# Tardis.net
KiCad netlist of a schematic drawn in EAGLE
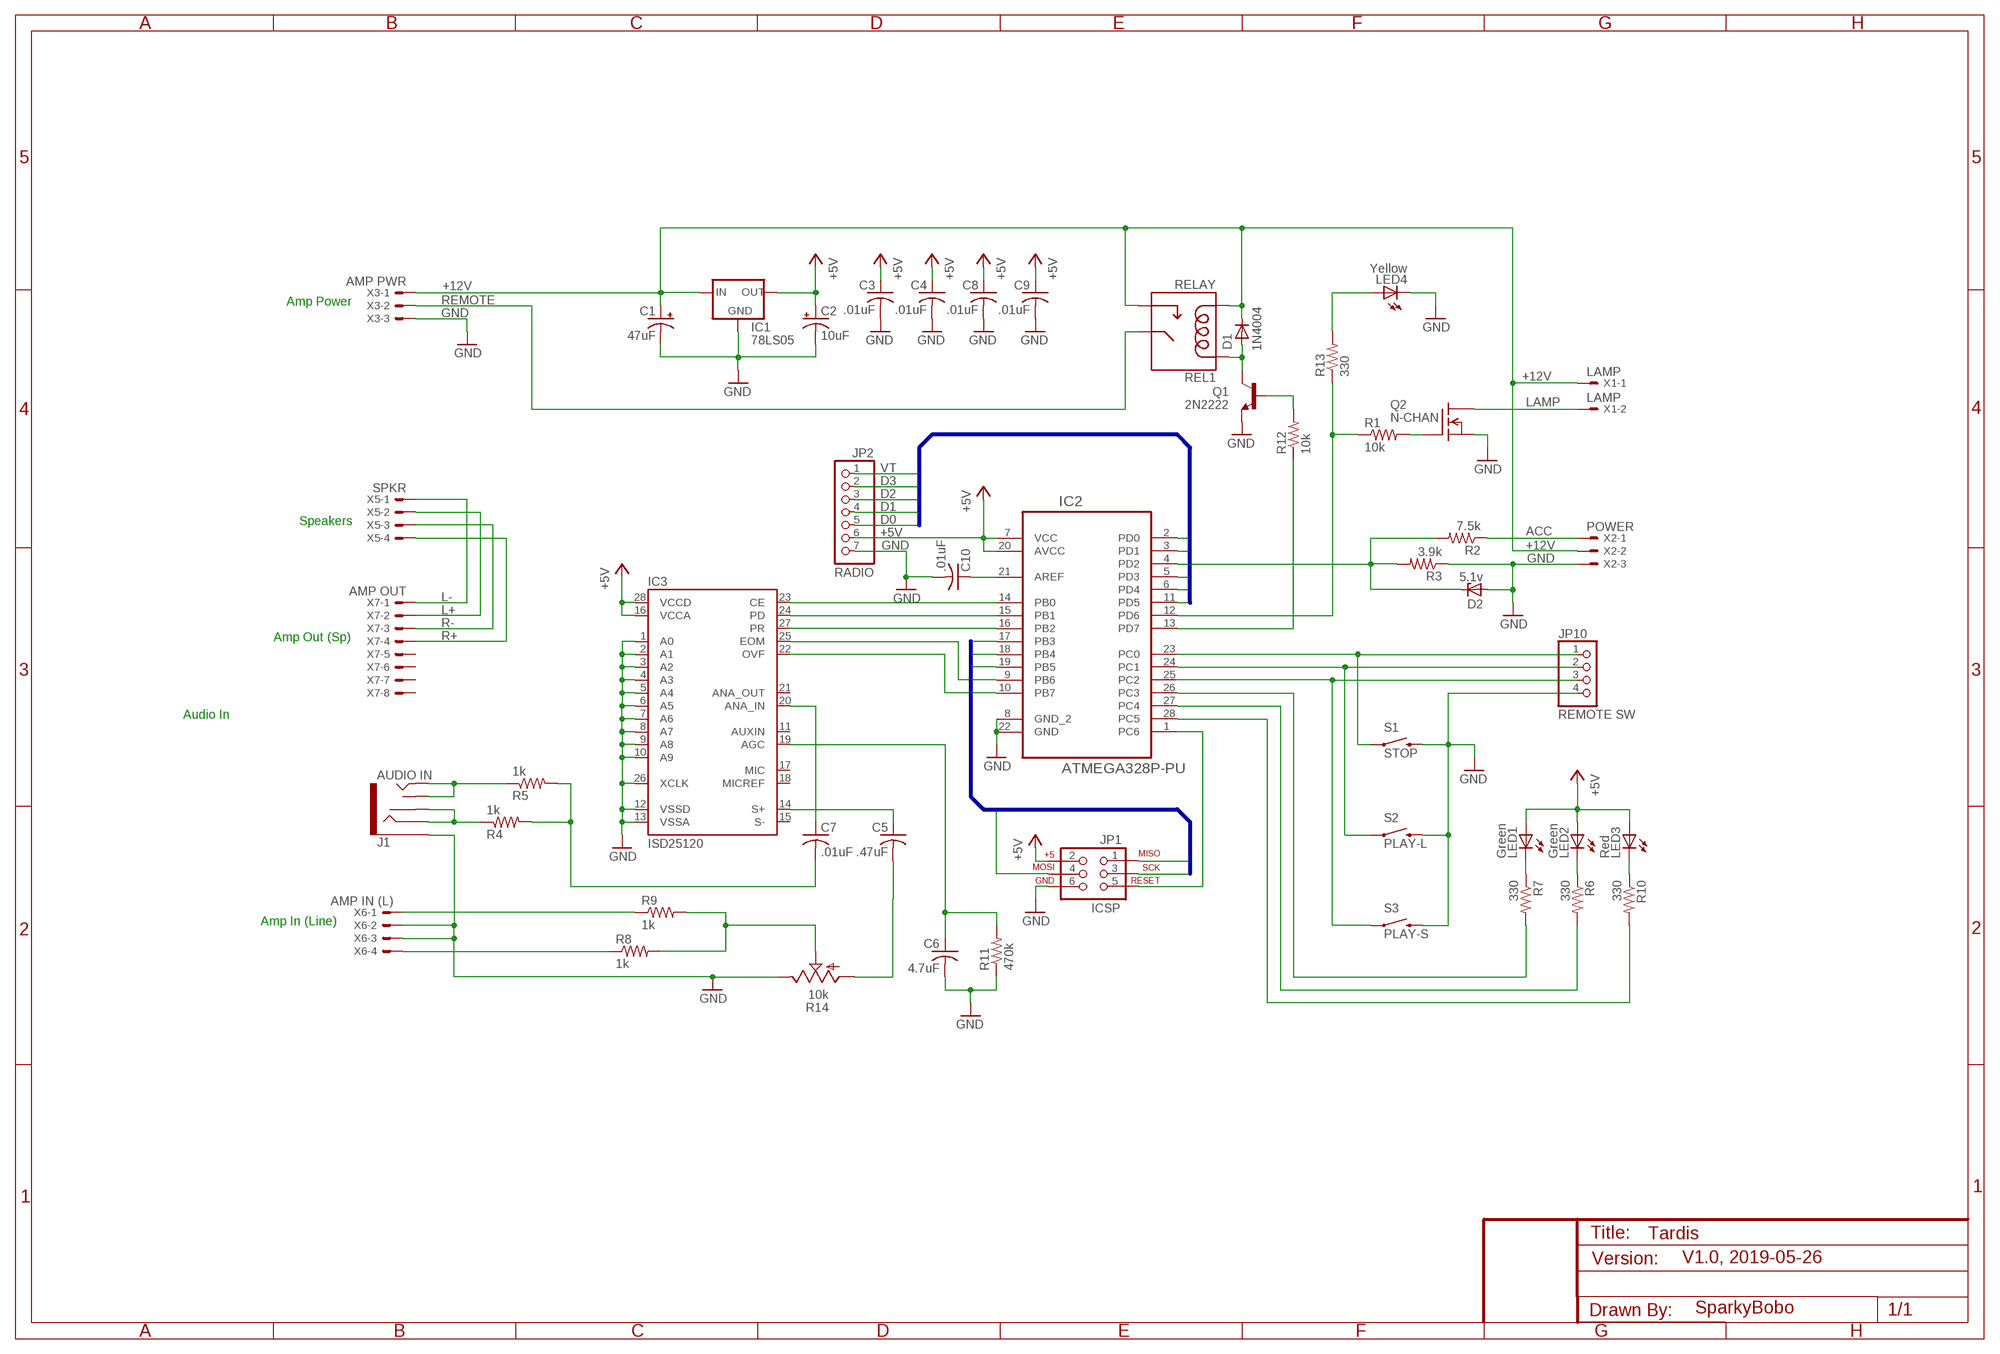
[diagram p0: schematic, sheet 1]

(export (version "E")
  (design (tool "Eeschema 10.0.6"))
  (components
    (comp (ref "C1")
      (value "47uF")
      (footprint "eagle-import:E3,5-8")
      (libsource (lib "eagle-import") (part "CPOL-USE3.5-8"))
    )
    (comp (ref "C2")
      (value "10uF")
      (footprint "eagle-import:E3,5-8")
      (libsource (lib "eagle-import") (part "CPOL-USE3.5-8"))
    )
    (comp (ref "C3")
      (value ".01uF")
      (footprint "eagle-import:C025-025X050")
      (libsource (lib "eagle-import") (part "C-US025-025X050"))
    )
    (comp (ref "C4")
      (value ".01uF")
      (footprint "eagle-import:C025-025X050")
      (libsource (lib "eagle-import") (part "C-US025-025X050"))
    )
    (comp (ref "C5")
      (value ".47uF")
      (footprint "eagle-import:C025-025X050")
      (libsource (lib "eagle-import") (part "C-US025-025X050"))
    )
    (comp (ref "C6")
      (value "4.7uF")
      (footprint "eagle-import:C025-025X050")
      (libsource (lib "eagle-import") (part "C-US025-025X050"))
    )
    (comp (ref "C7")
      (value ".01uF")
      (footprint "eagle-import:C050-025X075")
      (libsource (lib "eagle-import") (part "C-US050-025X075"))
    )
    (comp (ref "C8")
      (value ".01uF")
      (footprint "eagle-import:C025-025X050")
      (libsource (lib "eagle-import") (part "C-US025-025X050"))
    )
    (comp (ref "C9")
      (value ".01uF")
      (footprint "eagle-import:C025-025X050")
      (libsource (lib "eagle-import") (part "C-US025-025X050"))
    )
    (comp (ref "C10")
      (value ".01uF")
      (footprint "eagle-import:C025-025X050")
      (libsource (lib "eagle-import") (part "C-US025-025X050"))
    )
    (comp (ref "D1")
      (value "1N4004")
      (footprint "eagle-import:DIODE-1N4148")
      (libsource (lib "eagle-import") (part "DIODE1N4148"))
    )
    (comp (ref "D2")
      (value "5.1v")
      (footprint "eagle-import:DO35Z10")
      (libsource (lib "eagle-import") (part "ZENER-DIODEDO35Z10"))
    )
    (comp (ref "IC1")
      (value "78LS05")
      (footprint "eagle-import:TO-92")
      (libsource (lib "eagle-import") (part "V_REG_78XXTO-92"))
    )
    (comp (ref "IC2")
      (value "ATMEGA328P-PU")
      (footprint "eagle-import:DIP254P762X457-28")
      (libsource (lib "eagle-import") (part "ATMEGA328P-PU"))
    )
    (comp (ref "IC3")
      (value "ISD25120")
      (footprint "eagle-import:CRAZYGIRAFFE_DIL28-6")
      (libsource (lib "eagle-import") (part "CRAZYGIRAFFE_ISD25120"))
    )
    (comp (ref "J1")
      (value "AUDIO IN")
      (footprint "eagle-import:AUDIO-JACK")
      (libsource (lib "eagle-import") (part "AUDIO-JACK2PTH"))
    )
    (comp (ref "JP1")
      (value "ICSP")
      (footprint "eagle-import:2X3")
      (libsource (lib "eagle-import") (part "AVR_SPI_PRG_6PTH"))
    )
    (comp (ref "JP2")
      (value "RADIO")
      (footprint "eagle-import:1X07")
      (libsource (lib "eagle-import") (part "PINHD-1X7"))
    )
    (comp (ref "JP10")
      (value "REMOTE SW")
      (footprint "eagle-import:1X04")
      (libsource (lib "eagle-import") (part "PINHD-1X4"))
    )
    (comp (ref "LED1")
      (value "Green")
      (footprint "eagle-import:LED5MM")
      (libsource (lib "eagle-import") (part "LED5MM"))
    )
    (comp (ref "LED2")
      (value "Green")
      (footprint "eagle-import:LED5MM")
      (libsource (lib "eagle-import") (part "LED5MM"))
    )
    (comp (ref "LED3")
      (value "Red")
      (footprint "eagle-import:LED5MM")
      (libsource (lib "eagle-import") (part "LED5MM"))
    )
    (comp (ref "LED4")
      (value "Yellow")
      (footprint "eagle-import:LED5MM")
      (libsource (lib "eagle-import") (part "LED5MM"))
    )
    (comp (ref "Q1")
      (value "2N2222")
      (footprint "eagle-import:TO-92")
      (libsource (lib "eagle-import") (part "TRANSISTOR_NPNTO92"))
    )
    (comp (ref "Q2")
      (value "N-CHAN")
      (footprint "eagle-import:TO220")
      (libsource (lib "eagle-import") (part "BUZ10"))
    )
    (comp (ref "R1")
      (value "10k")
      (footprint "eagle-import:0207_10")
      (libsource (lib "eagle-import") (part "R-US_0207/10"))
    )
    (comp (ref "R2")
      (value "7.5k")
      (footprint "eagle-import:0207_10")
      (libsource (lib "eagle-import") (part "R-US_0207/10"))
    )
    (comp (ref "R3")
      (value "3.9k")
      (footprint "eagle-import:0207_10")
      (libsource (lib "eagle-import") (part "R-US_0207/10"))
    )
    (comp (ref "R4")
      (value "1k")
      (footprint "eagle-import:0207_10")
      (libsource (lib "eagle-import") (part "R-US_0207/10"))
    )
    (comp (ref "R5")
      (value "1k")
      (footprint "eagle-import:0207_10")
      (libsource (lib "eagle-import") (part "R-US_0207/10"))
    )
    (comp (ref "R6")
      (value "330")
      (footprint "eagle-import:0207_10")
      (libsource (lib "eagle-import") (part "R-US_0207/10"))
    )
    (comp (ref "R7")
      (value "330")
      (footprint "eagle-import:0207_10")
      (libsource (lib "eagle-import") (part "R-US_0207/10"))
    )
    (comp (ref "R8")
      (value "1k")
      (footprint "eagle-import:0207_10")
      (libsource (lib "eagle-import") (part "R-US_0207/10"))
    )
    (comp (ref "R9")
      (value "1k")
      (footprint "eagle-import:0207_10")
      (libsource (lib "eagle-import") (part "R-US_0207/10"))
    )
    (comp (ref "R10")
      (value "330")
      (footprint "eagle-import:0207_10")
      (libsource (lib "eagle-import") (part "R-US_0207/10"))
    )
    (comp (ref "R11")
      (value "470k")
      (footprint "eagle-import:0207_10")
      (libsource (lib "eagle-import") (part "R-US_0207/10"))
    )
    (comp (ref "R12")
      (value "10k")
      (footprint "eagle-import:0207_10")
      (libsource (lib "eagle-import") (part "R-US_0207/10"))
    )
    (comp (ref "R13")
      (value "330")
      (footprint "eagle-import:0207_10")
      (libsource (lib "eagle-import") (part "R-US_0207/10"))
    )
    (comp (ref "R14")
      (value "10k")
      (footprint "eagle-import:CA6V")
      (libsource (lib "eagle-import") (part "TRIM_US-CA6V"))
    )
    (comp (ref "REL1")
      (value "RELAY")
      (footprint "eagle-import:CRAZYGIRAFFE_RELAY-DIP")
      (libsource (lib "eagle-import") (part "CRAZYGIRAFFE_RELAY"))
    )
    (comp (ref "S1")
      (value "STOP")
      (footprint "eagle-import:CRAZYGIRAFFE_TACTILE-PTH-12MM")
      (libsource (lib "eagle-import") (part "CRAZYGIRAFFE_SWITCH-MOMENTARY-212MM"))
    )
    (comp (ref "S2")
      (value "PLAY-L")
      (footprint "eagle-import:CRAZYGIRAFFE_TACTILE-PTH-12MM")
      (libsource (lib "eagle-import") (part "CRAZYGIRAFFE_SWITCH-MOMENTARY-212MM"))
    )
    (comp (ref "S3")
      (value "PLAY-S")
      (footprint "eagle-import:CRAZYGIRAFFE_TACTILE-PTH-12MM")
      (libsource (lib "eagle-import") (part "CRAZYGIRAFFE_SWITCH-MOMENTARY-212MM"))
    )
    (comp (ref "X1")
      (value "LAMP")
      (footprint "eagle-import:KK-156-2")
      (libsource (lib "eagle-import") (part "KK-156-2"))
    )
    (comp (ref "X2")
      (value "POWER")
      (footprint "eagle-import:KK-156-3")
      (libsource (lib "eagle-import") (part "KK-156-3"))
    )
    (comp (ref "X3")
      (value "AMP PWR")
      (footprint "eagle-import:KK-156-3")
      (libsource (lib "eagle-import") (part "KK-156-3"))
    )
    (comp (ref "X5")
      (value "SPKR")
      (footprint "eagle-import:KK-156-4")
      (libsource (lib "eagle-import") (part "KK-156-4"))
    )
    (comp (ref "X6")
      (value "AMP IN (L)")
      (footprint "eagle-import:KK-156-4")
      (libsource (lib "eagle-import") (part "KK-156-4"))
    )
    (comp (ref "X7")
      (value "AMP OUT")
      (footprint "eagle-import:KK-156-8")
      (libsource (lib "eagle-import") (part "KK-156-8"))
    )
  )
  (nets
    (net (code "1") (name "+5V") (class "Default")
      (node (ref "C2") (pin "+") (pinfunction "+_+") (pintype "passive"))
      (node (ref "C3") (pin "1") (pinfunction "1_1") (pintype "passive"))
      (node (ref "C4") (pin "1") (pinfunction "1_1") (pintype "passive"))
      (node (ref "C8") (pin "1") (pinfunction "1_1") (pintype "passive"))
      (node (ref "C9") (pin "1") (pinfunction "1_1") (pintype "passive"))
      (node (ref "IC1") (pin "3") (pinfunction "OUT_3") (pintype "output"))
      (node (ref "IC2") (pin "20") (pinfunction "AVCC_20") (pintype "power_in"))
      (node (ref "IC2") (pin "7") (pinfunction "VCC_7") (pintype "power_in"))
      (node (ref "IC3") (pin "16") (pinfunction "VCCA_16") (pintype "power_in"))
      (node (ref "IC3") (pin "28") (pinfunction "VCCD_28") (pintype "power_in"))
      (node (ref "JP1") (pin "2") (pinfunction "2_2") (pintype "passive"))
      (node (ref "JP2") (pin "6") (pinfunction "6_6") (pintype "passive"))
      (node (ref "LED1") (pin "A") (pinfunction "A_A") (pintype "passive"))
      (node (ref "LED2") (pin "A") (pinfunction "A_A") (pintype "passive"))
      (node (ref "LED3") (pin "A") (pinfunction "A_A") (pintype "passive"))
    )
    (net (code "2") (name "/+12V") (class "Default")
      (node (ref "C1") (pin "+") (pinfunction "+_+") (pintype "passive"))
      (node (ref "D1") (pin "C") (pinfunction "C_C") (pintype "passive"))
      (node (ref "IC1") (pin "2") (pinfunction "IN_2") (pintype "input"))
      (node (ref "REL1") (pin "2") (pinfunction "COIL2_2") (pintype "bidirectional"))
      (node (ref "REL1") (pin "4") (pinfunction "NO_4") (pintype "bidirectional"))
      (node (ref "X1") (pin "1") (pinfunction "S_1") (pintype "passive"))
      (node (ref "X2") (pin "2") (pinfunction "S_2") (pintype "passive"))
      (node (ref "X3") (pin "1") (pinfunction "S_1") (pintype "passive"))
    )
    (net (code "3") (name "/ACC") (class "Default")
      (node (ref "R2") (pin "1") (pinfunction "1_1") (pintype "passive"))
      (node (ref "X2") (pin "1") (pinfunction "S_1") (pintype "passive"))
    )
    (net (code "4") (name "/D0") (class "Default")
      (node (ref "IC2") (pin "3") (pinfunction "PD1_3") (pintype "bidirectional"))
      (node (ref "JP2") (pin "5") (pinfunction "5_5") (pintype "passive"))
    )
    (net (code "5") (name "/D1") (class "Default")
      (node (ref "IC2") (pin "2") (pinfunction "PD0_2") (pintype "bidirectional"))
      (node (ref "JP2") (pin "4") (pinfunction "4_4") (pintype "passive"))
    )
    (net (code "6") (name "/D2") (class "Default")
      (node (ref "IC2") (pin "11") (pinfunction "PD5_11") (pintype "bidirectional"))
      (node (ref "JP2") (pin "3") (pinfunction "3_3") (pintype "passive"))
    )
    (net (code "7") (name "/D3") (class "Default")
      (node (ref "IC2") (pin "6") (pinfunction "PD4_6") (pintype "bidirectional"))
      (node (ref "JP2") (pin "2") (pinfunction "2_2") (pintype "passive"))
    )
    (net (code "8") (name "/L+") (class "Default")
      (node (ref "X5") (pin "2") (pinfunction "S_2") (pintype "passive"))
      (node (ref "X7") (pin "2") (pinfunction "S_2") (pintype "passive"))
    )
    (net (code "9") (name "/L-") (class "Default")
      (node (ref "X5") (pin "1") (pinfunction "S_1") (pintype "passive"))
      (node (ref "X7") (pin "1") (pinfunction "S_1") (pintype "passive"))
    )
    (net (code "10") (name "/LAMP") (class "Default")
      (node (ref "Q2") (pin "2") (pinfunction "D_2") (pintype "passive"))
      (node (ref "X1") (pin "2") (pinfunction "S_2") (pintype "passive"))
    )
    (net (code "11") (name "/MISO") (class "Default")
      (node (ref "IC2") (pin "18") (pinfunction "PB4_18") (pintype "bidirectional"))
      (node (ref "JP1") (pin "1") (pinfunction "1_1") (pintype "passive"))
    )
    (net (code "12") (name "/MOSI") (class "Default")
      (node (ref "IC2") (pin "17") (pinfunction "PB3_17") (pintype "bidirectional"))
      (node (ref "JP1") (pin "4") (pinfunction "4_4") (pintype "passive"))
    )
    (net (code "13") (name "/R+") (class "Default")
      (node (ref "X5") (pin "4") (pinfunction "S_4") (pintype "passive"))
      (node (ref "X7") (pin "4") (pinfunction "S_4") (pintype "passive"))
    )
    (net (code "14") (name "/R-") (class "Default")
      (node (ref "X5") (pin "3") (pinfunction "S_3") (pintype "passive"))
      (node (ref "X7") (pin "3") (pinfunction "S_3") (pintype "passive"))
    )
    (net (code "15") (name "/REMOTE") (class "Default")
      (node (ref "REL1") (pin "3") (pinfunction "MAIN_3") (pintype "bidirectional"))
      (node (ref "X3") (pin "2") (pinfunction "S_2") (pintype "passive"))
    )
    (net (code "16") (name "/SCK") (class "Default")
      (node (ref "IC2") (pin "19") (pinfunction "PB5_19") (pintype "bidirectional"))
      (node (ref "JP1") (pin "3") (pinfunction "3_3") (pintype "passive"))
    )
    (net (code "17") (name "/VT") (class "Default")
      (node (ref "IC2") (pin "5") (pinfunction "PD3_5") (pintype "bidirectional"))
      (node (ref "JP2") (pin "1") (pinfunction "1_1") (pintype "passive"))
    )
    (net (code "18") (name "GND") (class "Default")
      (node (ref "C1") (pin "-") (pinfunction "-_-") (pintype "passive"))
      (node (ref "C10") (pin "2") (pinfunction "2_2") (pintype "passive"))
      (node (ref "C2") (pin "-") (pinfunction "-_-") (pintype "passive"))
      (node (ref "C3") (pin "2") (pinfunction "2_2") (pintype "passive"))
      (node (ref "C4") (pin "2") (pinfunction "2_2") (pintype "passive"))
      (node (ref "C6") (pin "2") (pinfunction "2_2") (pintype "passive"))
      (node (ref "C8") (pin "2") (pinfunction "2_2") (pintype "passive"))
      (node (ref "C9") (pin "2") (pinfunction "2_2") (pintype "passive"))
      (node (ref "D2") (pin "A") (pinfunction "A_A") (pintype "passive"))
      (node (ref "IC1") (pin "1") (pinfunction "GND_1") (pintype "input"))
      (node (ref "IC2") (pin "22") (pinfunction "GND_22") (pintype "passive"))
      (node (ref "IC2") (pin "8") (pinfunction "GND_2_8") (pintype "passive"))
      (node (ref "IC3") (pin "1") (pinfunction "A0_1") (pintype "input"))
      (node (ref "IC3") (pin "10") (pinfunction "A9_10") (pintype "input"))
      (node (ref "IC3") (pin "12") (pinfunction "VSSD_12") (pintype "power_in"))
      (node (ref "IC3") (pin "13") (pinfunction "VSSA_13") (pintype "power_in"))
      (node (ref "IC3") (pin "2") (pinfunction "A1_2") (pintype "input"))
      (node (ref "IC3") (pin "26") (pinfunction "XCLK_26") (pintype "bidirectional"))
      (node (ref "IC3") (pin "3") (pinfunction "A2_3") (pintype "input"))
      (node (ref "IC3") (pin "4") (pinfunction "A3_4") (pintype "input"))
      (node (ref "IC3") (pin "5") (pinfunction "A4_5") (pintype "input"))
      (node (ref "IC3") (pin "6") (pinfunction "A5_6") (pintype "input"))
      (node (ref "IC3") (pin "7") (pinfunction "A6_7") (pintype "input"))
      (node (ref "IC3") (pin "8") (pinfunction "A7_8") (pintype "input"))
      (node (ref "IC3") (pin "9") (pinfunction "A8_9") (pintype "input"))
      (node (ref "J1") (pin "SLEEVE") (pinfunction "SLEEVE_SLEEVE") (pintype "bidirectional"))
      (node (ref "JP1") (pin "6") (pinfunction "6_6") (pintype "passive"))
      (node (ref "JP10") (pin "4") (pinfunction "4_4") (pintype "passive"))
      (node (ref "JP2") (pin "7") (pinfunction "7_7") (pintype "passive"))
      (node (ref "LED4") (pin "K") (pinfunction "C_K") (pintype "passive"))
      (node (ref "Q1") (pin "1") (pinfunction "E_1") (pintype "passive"))
      (node (ref "Q2") (pin "3") (pinfunction "S_3") (pintype "passive"))
      (node (ref "R11") (pin "1") (pinfunction "1_1") (pintype "passive"))
      (node (ref "R14") (pin "E") (pinfunction "E_E") (pintype "passive"))
      (node (ref "R3") (pin "1") (pinfunction "1_1") (pintype "passive"))
      (node (ref "S1") (pin "3") (pinfunction "2_3") (pintype "passive"))
      (node (ref "S2") (pin "3") (pinfunction "2_3") (pintype "passive"))
      (node (ref "S3") (pin "3") (pinfunction "2_3") (pintype "passive"))
      (node (ref "X2") (pin "3") (pinfunction "S_3") (pintype "passive"))
      (node (ref "X3") (pin "3") (pinfunction "S_3") (pintype "passive"))
      (node (ref "X6") (pin "2") (pinfunction "S_2") (pintype "passive"))
      (node (ref "X6") (pin "3") (pinfunction "S_3") (pintype "passive"))
    )
    (net (code "19") (name "Net-(C5-Pad2)") (class "Default")
      (node (ref "C5") (pin "2") (pinfunction "2_2") (pintype "passive"))
      (node (ref "R14") (pin "A") (pinfunction "A_A") (pintype "passive"))
    )
    (net (code "20") (name "Net-(C7-Pad2)") (class "Default")
      (node (ref "C7") (pin "2") (pinfunction "2_2") (pintype "passive"))
      (node (ref "R4") (pin "2") (pinfunction "2_2") (pintype "passive"))
      (node (ref "R5") (pin "2") (pinfunction "2_2") (pintype "passive"))
    )
    (net (code "21") (name "Net-(IC2-AREF)") (class "Default")
      (node (ref "C10") (pin "1") (pinfunction "1_1") (pintype "passive"))
      (node (ref "IC2") (pin "21") (pinfunction "AREF_21") (pintype "input"))
    )
    (net (code "22") (name "Net-(IC2-PB0)") (class "Default")
      (node (ref "IC2") (pin "14") (pinfunction "PB0_14") (pintype "bidirectional"))
      (node (ref "IC3") (pin "23") (pinfunction "CE_23") (pintype "bidirectional"))
    )
    (net (code "23") (name "Net-(IC2-PB1)") (class "Default")
      (node (ref "IC2") (pin "15") (pinfunction "PB1_15") (pintype "bidirectional"))
      (node (ref "IC3") (pin "24") (pinfunction "PD_24") (pintype "bidirectional"))
    )
    (net (code "24") (name "Net-(IC2-PB2)") (class "Default")
      (node (ref "IC2") (pin "16") (pinfunction "PB2_16") (pintype "bidirectional"))
      (node (ref "IC3") (pin "27") (pinfunction "PR_27") (pintype "bidirectional"))
    )
    (net (code "25") (name "Net-(IC2-PB6)") (class "Default")
      (node (ref "IC2") (pin "9") (pinfunction "PB6_9") (pintype "bidirectional"))
      (node (ref "IC3") (pin "25") (pinfunction "EOM_25") (pintype "bidirectional"))
    )
    (net (code "26") (name "Net-(IC2-PB7)") (class "Default")
      (node (ref "IC2") (pin "10") (pinfunction "PB7_10") (pintype "bidirectional"))
      (node (ref "IC3") (pin "22") (pinfunction "OVF_22") (pintype "bidirectional"))
    )
    (net (code "27") (name "Net-(IC2-PC0)") (class "Default")
      (node (ref "IC2") (pin "23") (pinfunction "PC0_23") (pintype "bidirectional"))
      (node (ref "JP10") (pin "1") (pinfunction "1_1") (pintype "passive"))
      (node (ref "S1") (pin "1") (pinfunction "1_1") (pintype "passive"))
    )
    (net (code "28") (name "Net-(IC2-PC1)") (class "Default")
      (node (ref "IC2") (pin "24") (pinfunction "PC1_24") (pintype "bidirectional"))
      (node (ref "JP10") (pin "2") (pinfunction "2_2") (pintype "passive"))
      (node (ref "S2") (pin "1") (pinfunction "1_1") (pintype "passive"))
    )
    (net (code "29") (name "Net-(IC2-PC2)") (class "Default")
      (node (ref "IC2") (pin "25") (pinfunction "PC2_25") (pintype "bidirectional"))
      (node (ref "JP10") (pin "3") (pinfunction "3_3") (pintype "passive"))
      (node (ref "S3") (pin "1") (pinfunction "1_1") (pintype "passive"))
    )
    (net (code "30") (name "Net-(IC2-PC3)") (class "Default")
      (node (ref "IC2") (pin "26") (pinfunction "PC3_26") (pintype "bidirectional"))
      (node (ref "R7") (pin "2") (pinfunction "2_2") (pintype "passive"))
    )
    (net (code "31") (name "Net-(IC2-PC4)") (class "Default")
      (node (ref "IC2") (pin "27") (pinfunction "PC4_27") (pintype "bidirectional"))
      (node (ref "R6") (pin "2") (pinfunction "2_2") (pintype "passive"))
    )
    (net (code "32") (name "Net-(IC2-PC5)") (class "Default")
      (node (ref "IC2") (pin "28") (pinfunction "PC5_28") (pintype "bidirectional"))
      (node (ref "R10") (pin "2") (pinfunction "2_2") (pintype "passive"))
    )
    (net (code "33") (name "Net-(IC2-PC6)") (class "Default")
      (node (ref "IC2") (pin "1") (pinfunction "PC6_1") (pintype "bidirectional"))
      (node (ref "JP1") (pin "5") (pinfunction "5_5") (pintype "passive"))
    )
    (net (code "34") (name "Net-(IC2-PD2)") (class "Default")
      (node (ref "D2") (pin "C") (pinfunction "C_C") (pintype "passive"))
      (node (ref "IC2") (pin "4") (pinfunction "PD2_4") (pintype "bidirectional"))
      (node (ref "R2") (pin "2") (pinfunction "2_2") (pintype "passive"))
      (node (ref "R3") (pin "2") (pinfunction "2_2") (pintype "passive"))
    )
    (net (code "35") (name "Net-(IC2-PD6)") (class "Default")
      (node (ref "IC2") (pin "12") (pinfunction "PD6_12") (pintype "bidirectional"))
      (node (ref "R1") (pin "1") (pinfunction "1_1") (pintype "passive"))
      (node (ref "R13") (pin "1") (pinfunction "1_1") (pintype "passive"))
    )
    (net (code "36") (name "Net-(IC2-PD7)") (class "Default")
      (node (ref "IC2") (pin "13") (pinfunction "PD7_13") (pintype "bidirectional"))
      (node (ref "R12") (pin "1") (pinfunction "1_1") (pintype "passive"))
    )
    (net (code "37") (name "Net-(IC3-AGC)") (class "Default")
      (node (ref "C6") (pin "1") (pinfunction "1_1") (pintype "passive"))
      (node (ref "IC3") (pin "19") (pinfunction "AGC_19") (pintype "bidirectional"))
      (node (ref "R11") (pin "2") (pinfunction "2_2") (pintype "passive"))
    )
    (net (code "38") (name "Net-(IC3-ANA_IN)") (class "Default")
      (node (ref "C7") (pin "1") (pinfunction "1_1") (pintype "passive"))
      (node (ref "IC3") (pin "20") (pinfunction "ANA_IN_20") (pintype "bidirectional"))
    )
    (net (code "39") (name "Net-(IC3-S+)") (class "Default")
      (node (ref "C5") (pin "1") (pinfunction "1_1") (pintype "passive"))
      (node (ref "IC3") (pin "14") (pinfunction "S+_14") (pintype "bidirectional"))
    )
    (net (code "40") (name "Net-(J1-PadRING)") (class "Default")
      (node (ref "J1") (pin "RING") (pinfunction "RING_RING") (pintype "bidirectional"))
      (node (ref "J1") (pin "RSH") (pinfunction "RSH_RSH") (pintype "bidirectional"))
      (node (ref "R4") (pin "1") (pinfunction "1_1") (pintype "passive"))
    )
    (net (code "41") (name "Net-(J1-PadTIP)") (class "Default")
      (node (ref "J1") (pin "TIP") (pinfunction "TIP_TIP") (pintype "bidirectional"))
      (node (ref "J1") (pin "TSH") (pinfunction "TSH_TSH") (pintype "bidirectional"))
      (node (ref "R5") (pin "1") (pinfunction "1_1") (pintype "passive"))
    )
    (net (code "42") (name "Net-(LED1-C)") (class "Default")
      (node (ref "LED1") (pin "K") (pinfunction "C_K") (pintype "passive"))
      (node (ref "R7") (pin "1") (pinfunction "1_1") (pintype "passive"))
    )
    (net (code "43") (name "Net-(LED2-C)") (class "Default")
      (node (ref "LED2") (pin "K") (pinfunction "C_K") (pintype "passive"))
      (node (ref "R6") (pin "1") (pinfunction "1_1") (pintype "passive"))
    )
    (net (code "44") (name "Net-(LED3-C)") (class "Default")
      (node (ref "LED3") (pin "K") (pinfunction "C_K") (pintype "passive"))
      (node (ref "R10") (pin "1") (pinfunction "1_1") (pintype "passive"))
    )
    (net (code "45") (name "Net-(LED4-PadA)") (class "Default")
      (node (ref "LED4") (pin "A") (pinfunction "A_A") (pintype "passive"))
      (node (ref "R13") (pin "2") (pinfunction "2_2") (pintype "passive"))
    )
    (net (code "46") (name "Net-(Q1-B)") (class "Default")
      (node (ref "Q1") (pin "2") (pinfunction "B_2") (pintype "passive"))
      (node (ref "R12") (pin "2") (pinfunction "2_2") (pintype "passive"))
    )
    (net (code "47") (name "Net-(Q1-C)") (class "Default")
      (node (ref "D1") (pin "A") (pinfunction "A_A") (pintype "passive"))
      (node (ref "Q1") (pin "3") (pinfunction "C_3") (pintype "passive"))
      (node (ref "REL1") (pin "1") (pinfunction "COIL1_1") (pintype "bidirectional"))
    )
    (net (code "48") (name "Net-(Q2-G)") (class "Default")
      (node (ref "Q2") (pin "1") (pinfunction "G_1") (pintype "passive"))
      (node (ref "R1") (pin "2") (pinfunction "2_2") (pintype "passive"))
    )
    (net (code "49") (name "Net-(R14-PadS)") (class "Default")
      (node (ref "R14") (pin "S") (pinfunction "S_S") (pintype "passive"))
      (node (ref "R8") (pin "2") (pinfunction "2_2") (pintype "passive"))
      (node (ref "R9") (pin "2") (pinfunction "2_2") (pintype "passive"))
    )
    (net (code "50") (name "Net-(X6A-S)") (class "Default")
      (node (ref "R9") (pin "1") (pinfunction "1_1") (pintype "passive"))
      (node (ref "X6") (pin "1") (pinfunction "S_1") (pintype "passive"))
    )
    (net (code "51") (name "Net-(X6D-S)") (class "Default")
      (node (ref "R8") (pin "1") (pinfunction "1_1") (pintype "passive"))
      (node (ref "X6") (pin "4") (pinfunction "S_4") (pintype "passive"))
    )
    (net (code "52") (name "unconnected-(IC3-ANA_OUT-Pad21)") (class "Default")
      (node (ref "IC3") (pin "21") (pinfunction "ANA_OUT_21") (pintype "bidirectional"))
    )
    (net (code "53") (name "unconnected-(IC3-AUXIN-Pad11)") (class "Default")
      (node (ref "IC3") (pin "11") (pinfunction "AUXIN_11") (pintype "bidirectional"))
    )
    (net (code "54") (name "unconnected-(IC3-MIC-Pad17)") (class "Default")
      (node (ref "IC3") (pin "17") (pinfunction "MIC_17") (pintype "bidirectional"))
    )
    (net (code "55") (name "unconnected-(IC3-MICREF-Pad18)") (class "Default")
      (node (ref "IC3") (pin "18") (pinfunction "MICREF_18") (pintype "bidirectional"))
    )
    (net (code "56") (name "unconnected-(IC3-S--Pad15)") (class "Default")
      (node (ref "IC3") (pin "15") (pinfunction "S-_15") (pintype "bidirectional"))
    )
    (net (code "57") (name "unconnected-(X7E-S-Pad5)") (class "Default")
      (node (ref "X7") (pin "5") (pinfunction "S_5") (pintype "passive"))
    )
    (net (code "58") (name "unconnected-(X7F-S-Pad6)") (class "Default")
      (node (ref "X7") (pin "6") (pinfunction "S_6") (pintype "passive"))
    )
    (net (code "59") (name "unconnected-(X7G-S-Pad7)") (class "Default")
      (node (ref "X7") (pin "7") (pinfunction "S_7") (pintype "passive"))
    )
    (net (code "60") (name "unconnected-(X7H-S-Pad8)") (class "Default")
      (node (ref "X7") (pin "8") (pinfunction "S_8") (pintype "passive"))
    )
  )
)
